# SoilCape.net
KiCad netlist of a schematic drawn in EAGLE
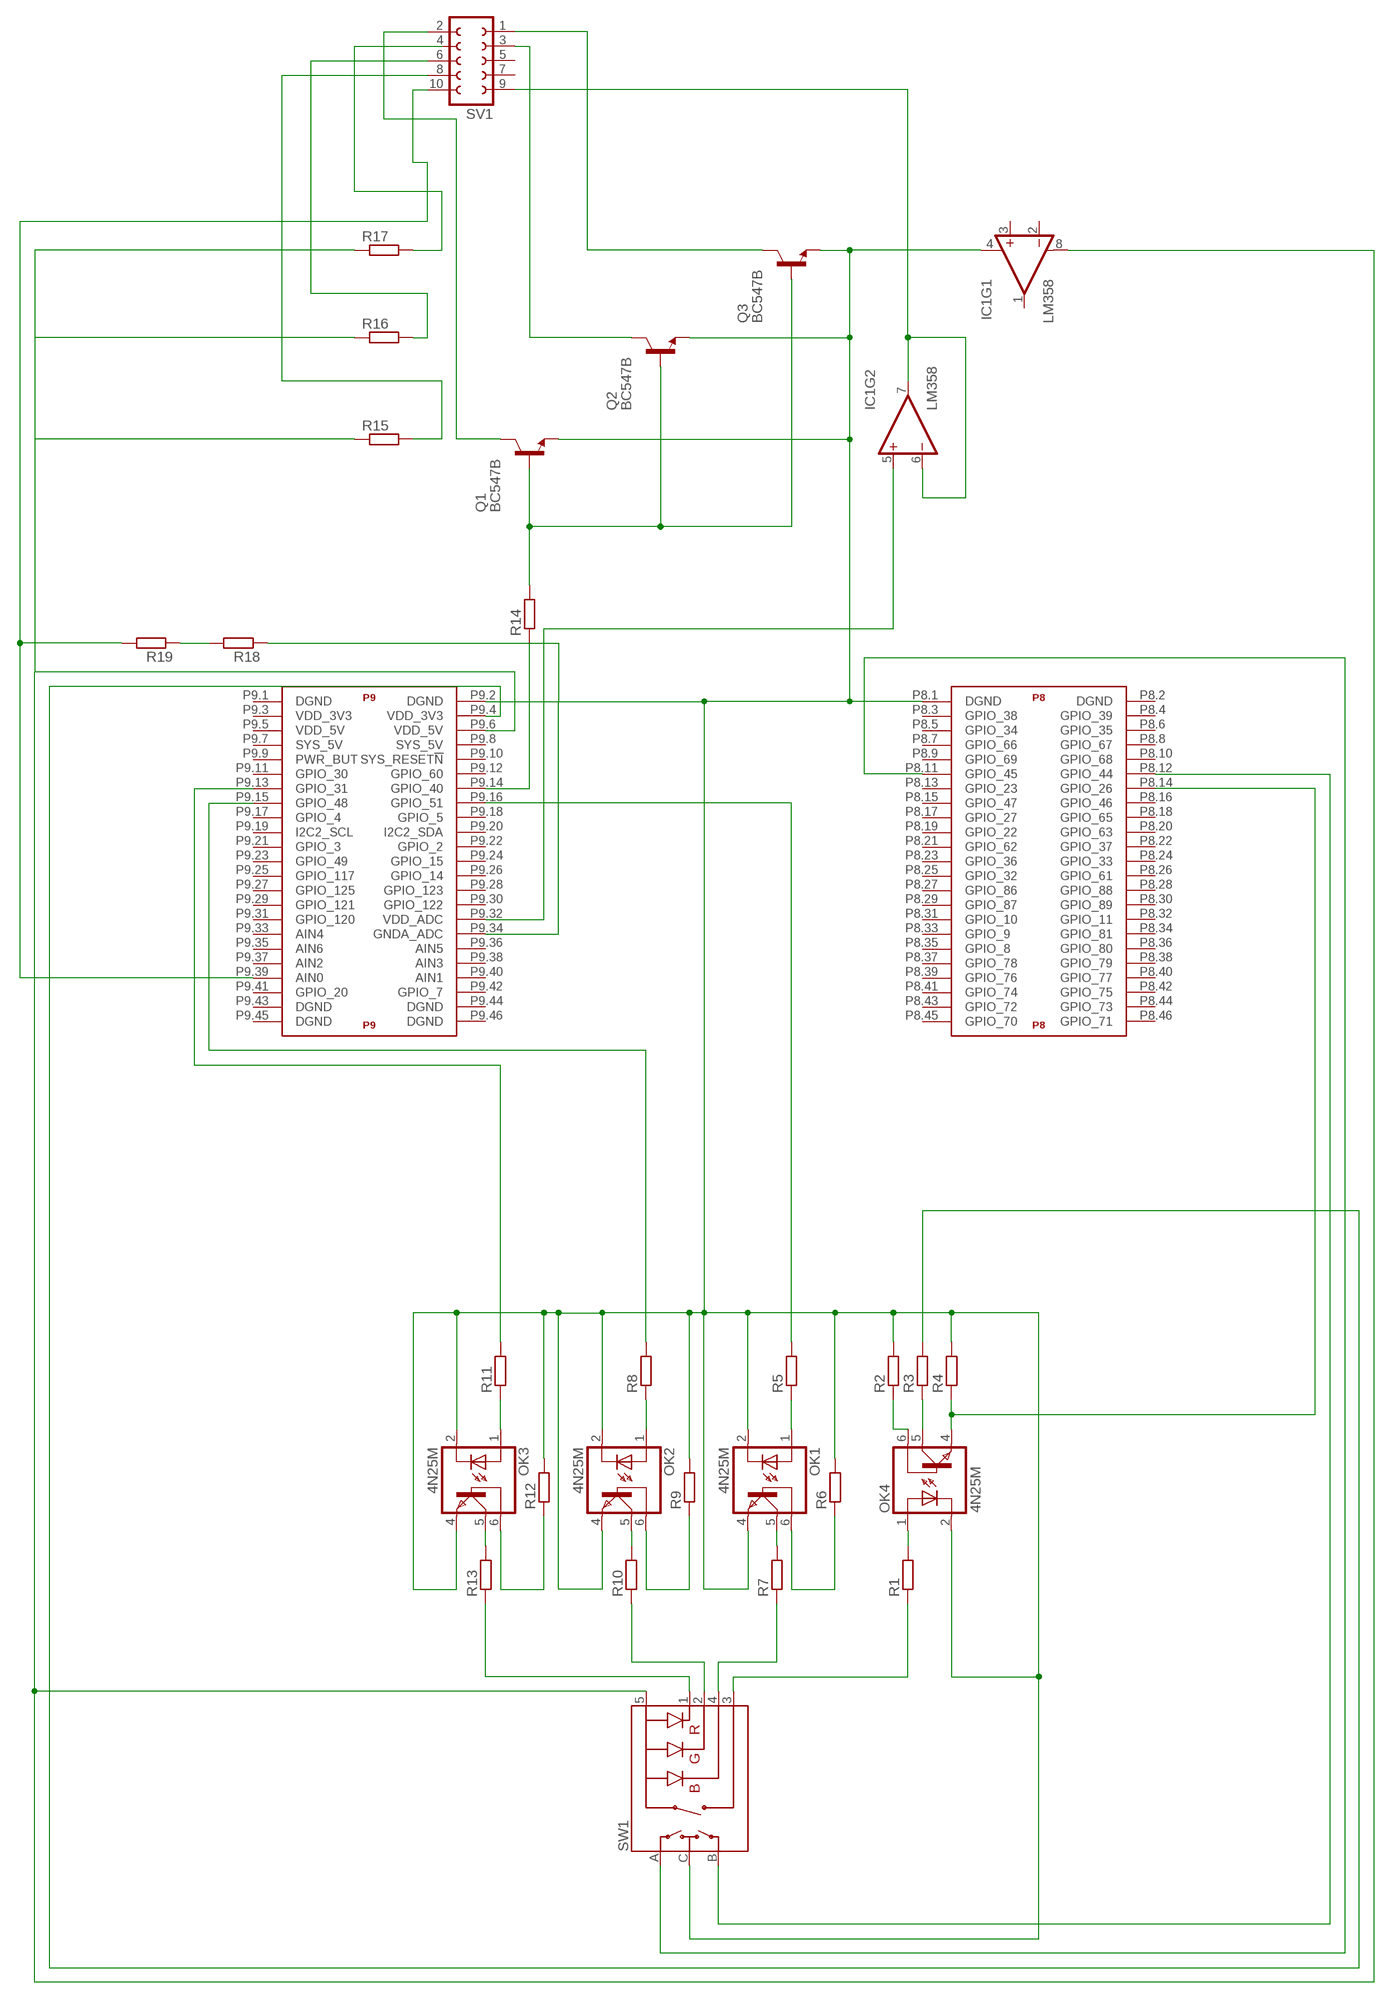
[diagram p0: schematic, sheet 1]

(export (version "E")
  (design (tool "Eeschema 10.0.6"))
  (components
    (comp (ref "IC1")
      (value "LM358")
      (footprint "eagle-import:DIP08")
      (libsource (lib "eagle-import") (part "LM358"))
    )
    (comp (ref "OK1")
      (value "4N25M")
      (footprint "eagle-import:DIL06")
      (fields (field (name "MPN") "4N25-M"))
      (libsource (lib "eagle-import") (part "4N?M25"))
    )
    (comp (ref "OK2")
      (value "4N25M")
      (footprint "eagle-import:DIL06")
      (fields (field (name "MPN") "4N25-M"))
      (libsource (lib "eagle-import") (part "4N?M25"))
    )
    (comp (ref "OK3")
      (value "4N25M")
      (footprint "eagle-import:DIL06")
      (fields (field (name "MPN") "4N25-M"))
      (libsource (lib "eagle-import") (part "4N?M25"))
    )
    (comp (ref "OK4")
      (value "4N25M")
      (footprint "eagle-import:DIL06")
      (fields (field (name "MPN") "4N25-M"))
      (libsource (lib "eagle-import") (part "4N?M25"))
    )
    (comp (ref "Q1")
      (value "BC547B")
      (footprint "eagle-import:TO92")
      (libsource (lib "eagle-import") (part "BC547B"))
    )
    (comp (ref "Q2")
      (value "BC547B")
      (footprint "eagle-import:TO92")
      (libsource (lib "eagle-import") (part "BC547B"))
    )
    (comp (ref "Q3")
      (value "BC547B")
      (footprint "eagle-import:TO92")
      (libsource (lib "eagle-import") (part "BC547B"))
    )
    (comp (ref "R1")
      (value "R-EU_0204/7")
      (footprint "eagle-import:0204_7")
      (libsource (lib "eagle-import") (part "R-EU_0204/7"))
    )
    (comp (ref "R2")
      (value "R-EU_0204/7")
      (footprint "eagle-import:0204_7")
      (libsource (lib "eagle-import") (part "R-EU_0204/7"))
    )
    (comp (ref "R3")
      (value "R-EU_0204/7")
      (footprint "eagle-import:0204_7")
      (libsource (lib "eagle-import") (part "R-EU_0204/7"))
    )
    (comp (ref "R4")
      (value "R-EU_0204/7")
      (footprint "eagle-import:0204_7")
      (libsource (lib "eagle-import") (part "R-EU_0204/7"))
    )
    (comp (ref "R5")
      (value "R-EU_0204/7")
      (footprint "eagle-import:0204_7")
      (libsource (lib "eagle-import") (part "R-EU_0204/7"))
    )
    (comp (ref "R6")
      (value "R-EU_0204/7")
      (footprint "eagle-import:0204_7")
      (libsource (lib "eagle-import") (part "R-EU_0204/7"))
    )
    (comp (ref "R7")
      (value "R-EU_0204/7")
      (footprint "eagle-import:0204_7")
      (libsource (lib "eagle-import") (part "R-EU_0204/7"))
    )
    (comp (ref "R8")
      (value "R-EU_0204/7")
      (footprint "eagle-import:0204_7")
      (libsource (lib "eagle-import") (part "R-EU_0204/7"))
    )
    (comp (ref "R9")
      (value "R-EU_0204/7")
      (footprint "eagle-import:0204_7")
      (libsource (lib "eagle-import") (part "R-EU_0204/7"))
    )
    (comp (ref "R10")
      (value "R-EU_0204/7")
      (footprint "eagle-import:0204_7")
      (libsource (lib "eagle-import") (part "R-EU_0204/7"))
    )
    (comp (ref "R11")
      (value "R-EU_0204/7")
      (footprint "eagle-import:0204_7")
      (libsource (lib "eagle-import") (part "R-EU_0204/7"))
    )
    (comp (ref "R12")
      (value "R-EU_0204/7")
      (footprint "eagle-import:0204_7")
      (libsource (lib "eagle-import") (part "R-EU_0204/7"))
    )
    (comp (ref "R13")
      (value "R-EU_0204/7")
      (footprint "eagle-import:0204_7")
      (libsource (lib "eagle-import") (part "R-EU_0204/7"))
    )
    (comp (ref "R14")
      (value "R-EU_0204/7")
      (footprint "eagle-import:0204_7")
      (libsource (lib "eagle-import") (part "R-EU_0204/7"))
    )
    (comp (ref "R15")
      (value "R-EU_0204/7")
      (footprint "eagle-import:0204_7")
      (libsource (lib "eagle-import") (part "R-EU_0204/7"))
    )
    (comp (ref "R16")
      (value "R-EU_0204/7")
      (footprint "eagle-import:0204_7")
      (libsource (lib "eagle-import") (part "R-EU_0204/7"))
    )
    (comp (ref "R17")
      (value "R-EU_0204/7")
      (footprint "eagle-import:0204_7")
      (libsource (lib "eagle-import") (part "R-EU_0204/7"))
    )
    (comp (ref "R18")
      (value "R-EU_0204/7")
      (footprint "eagle-import:0204_7")
      (libsource (lib "eagle-import") (part "R-EU_0204/7"))
    )
    (comp (ref "R19")
      (value "R-EU_0204/7")
      (footprint "eagle-import:0204_7")
      (libsource (lib "eagle-import") (part "R-EU_0204/7"))
    )
    (comp (ref "SV1")
      (value "FE05-2")
      (footprint "eagle-import:FE05-2")
      (libsource (lib "eagle-import") (part "FE05-2"))
    )
    (comp (ref "SW1")
      (value "ENCODER_RGB_CA")
      (footprint "eagle-import:ENCODER_LED_3")
      (libsource (lib "eagle-import") (part "ENCODER_RGB_CA"))
    )
    (comp (ref "U$1")
      (value "BEAGLE_BONE_BLACK_CAPE")
      (footprint "eagle-import:BEAGLE_BONE_BLACK_CAPE")
      (libsource (lib "eagle-import") (part "BEAGLE_BONE_BLACK_CAPE"))
    )
  )
  (nets
    (net (code "1") (name "Net-(IC1A-V+)") (class "Default")
      (node (ref "IC1") (pin "8") (pinfunction "V+_8") (pintype "power_in"))
      (node (ref "R15") (pin "1") (pinfunction "1_1") (pintype "passive"))
      (node (ref "R16") (pin "1") (pinfunction "1_1") (pintype "passive"))
      (node (ref "R17") (pin "1") (pinfunction "1_1") (pintype "passive"))
      (node (ref "SW1") (pin "5") (pinfunction "+_5") (pintype "passive"))
      (node (ref "U$1") (pin "P9.6") (pinfunction "VDD_5V_P9.6") (pintype "bidirectional"))
    )
    (net (code "2") (name "Net-(IC1A-V-)") (class "Default")
      (node (ref "IC1") (pin "4") (pinfunction "V-_4") (pintype "power_in"))
      (node (ref "OK1") (pin "2") (pinfunction "C_2") (pintype "passive"))
      (node (ref "OK1") (pin "4") (pinfunction "EMI_4") (pintype "passive"))
      (node (ref "OK2") (pin "2") (pinfunction "C_2") (pintype "passive"))
      (node (ref "OK2") (pin "4") (pinfunction "EMI_4") (pintype "passive"))
      (node (ref "OK3") (pin "2") (pinfunction "C_2") (pintype "passive"))
      (node (ref "OK3") (pin "4") (pinfunction "EMI_4") (pintype "passive"))
      (node (ref "OK4") (pin "2") (pinfunction "C_2") (pintype "passive"))
      (node (ref "Q1") (pin "1") (pinfunction "E_1") (pintype "passive"))
      (node (ref "Q2") (pin "1") (pinfunction "E_1") (pintype "passive"))
      (node (ref "Q3") (pin "1") (pinfunction "E_1") (pintype "passive"))
      (node (ref "R12") (pin "2") (pinfunction "2_2") (pintype "passive"))
      (node (ref "R18") (pin "1") (pinfunction "1_1") (pintype "passive"))
      (node (ref "R2") (pin "2") (pinfunction "2_2") (pintype "passive"))
      (node (ref "R4") (pin "2") (pinfunction "2_2") (pintype "passive"))
      (node (ref "R6") (pin "2") (pinfunction "2_2") (pintype "passive"))
      (node (ref "R9") (pin "2") (pinfunction "2_2") (pintype "passive"))
      (node (ref "SW1") (pin "C") (pinfunction "C_C") (pintype "bidirectional"))
      (node (ref "U$1") (pin "P8.1") (pinfunction "DGND_P8.1") (pintype "bidirectional"))
      (node (ref "U$1") (pin "P9.2") (pinfunction "DGND_P9.2") (pintype "bidirectional"))
      (node (ref "U$1") (pin "P9.34") (pinfunction "GNDA_ADC_P9.34") (pintype "bidirectional"))
    )
    (net (code "3") (name "Net-(IC1B-+IN)") (class "Default")
      (node (ref "IC1") (pin "5") (pinfunction "+IN_5") (pintype "input"))
      (node (ref "U$1") (pin "P9.32") (pinfunction "VDD_ADC_P9.32") (pintype "bidirectional"))
    )
    (net (code "4") (name "Net-(IC1B--IN)") (class "Default")
      (node (ref "IC1") (pin "6") (pinfunction "-IN_6") (pintype "input"))
      (node (ref "IC1") (pin "7") (pinfunction "OUT_7") (pintype "output"))
      (node (ref "SV1") (pin "9") (pinfunction "9_9") (pintype "passive"))
    )
    (net (code "5") (name "Net-(OK1-A)") (class "Default")
      (node (ref "OK1") (pin "1") (pinfunction "A_1") (pintype "passive"))
      (node (ref "R5") (pin "1") (pinfunction "1_1") (pintype "passive"))
    )
    (net (code "6") (name "Net-(OK1-BAS)") (class "Default")
      (node (ref "OK1") (pin "6") (pinfunction "BAS_6") (pintype "passive"))
      (node (ref "R6") (pin "1") (pinfunction "1_1") (pintype "passive"))
    )
    (net (code "7") (name "Net-(OK1-COL)") (class "Default")
      (node (ref "OK1") (pin "5") (pinfunction "COL_5") (pintype "passive"))
      (node (ref "R7") (pin "2") (pinfunction "2_2") (pintype "passive"))
    )
    (net (code "8") (name "Net-(OK2-A)") (class "Default")
      (node (ref "OK2") (pin "1") (pinfunction "A_1") (pintype "passive"))
      (node (ref "R8") (pin "1") (pinfunction "1_1") (pintype "passive"))
    )
    (net (code "9") (name "Net-(OK2-BAS)") (class "Default")
      (node (ref "OK2") (pin "6") (pinfunction "BAS_6") (pintype "passive"))
      (node (ref "R9") (pin "1") (pinfunction "1_1") (pintype "passive"))
    )
    (net (code "10") (name "Net-(OK2-COL)") (class "Default")
      (node (ref "OK2") (pin "5") (pinfunction "COL_5") (pintype "passive"))
      (node (ref "R10") (pin "2") (pinfunction "2_2") (pintype "passive"))
    )
    (net (code "11") (name "Net-(OK3-A)") (class "Default")
      (node (ref "OK3") (pin "1") (pinfunction "A_1") (pintype "passive"))
      (node (ref "R11") (pin "1") (pinfunction "1_1") (pintype "passive"))
    )
    (net (code "12") (name "Net-(OK3-BAS)") (class "Default")
      (node (ref "OK3") (pin "6") (pinfunction "BAS_6") (pintype "passive"))
      (node (ref "R12") (pin "1") (pinfunction "1_1") (pintype "passive"))
    )
    (net (code "13") (name "Net-(OK3-COL)") (class "Default")
      (node (ref "OK3") (pin "5") (pinfunction "COL_5") (pintype "passive"))
      (node (ref "R13") (pin "2") (pinfunction "2_2") (pintype "passive"))
    )
    (net (code "14") (name "Net-(OK4-A)") (class "Default")
      (node (ref "OK4") (pin "1") (pinfunction "A_1") (pintype "passive"))
      (node (ref "R1") (pin "2") (pinfunction "2_2") (pintype "passive"))
    )
    (net (code "15") (name "Net-(OK4-BAS)") (class "Default")
      (node (ref "OK4") (pin "6") (pinfunction "BAS_6") (pintype "passive"))
      (node (ref "R2") (pin "1") (pinfunction "1_1") (pintype "passive"))
    )
    (net (code "16") (name "Net-(OK4-COL)") (class "Default")
      (node (ref "OK4") (pin "5") (pinfunction "COL_5") (pintype "passive"))
      (node (ref "R3") (pin "1") (pinfunction "1_1") (pintype "passive"))
    )
    (net (code "17") (name "Net-(OK4-EMI)") (class "Default")
      (node (ref "OK4") (pin "4") (pinfunction "EMI_4") (pintype "passive"))
      (node (ref "R4") (pin "1") (pinfunction "1_1") (pintype "passive"))
      (node (ref "U$1") (pin "P8.14") (pinfunction "GPIO_26_P8.14") (pintype "bidirectional"))
    )
    (net (code "18") (name "Net-(Q1-B)") (class "Default")
      (node (ref "Q1") (pin "2") (pinfunction "B_2") (pintype "passive"))
      (node (ref "Q2") (pin "2") (pinfunction "B_2") (pintype "passive"))
      (node (ref "Q3") (pin "2") (pinfunction "B_2") (pintype "passive"))
      (node (ref "R14") (pin "2") (pinfunction "2_2") (pintype "passive"))
    )
    (net (code "19") (name "Net-(Q1-C)") (class "Default")
      (node (ref "Q1") (pin "3") (pinfunction "C_3") (pintype "passive"))
      (node (ref "SV1") (pin "2") (pinfunction "2_2") (pintype "passive"))
    )
    (net (code "20") (name "Net-(Q2-C)") (class "Default")
      (node (ref "Q2") (pin "3") (pinfunction "C_3") (pintype "passive"))
      (node (ref "SV1") (pin "3") (pinfunction "3_3") (pintype "passive"))
    )
    (net (code "21") (name "Net-(Q3-C)") (class "Default")
      (node (ref "Q3") (pin "3") (pinfunction "C_3") (pintype "passive"))
      (node (ref "SV1") (pin "1") (pinfunction "1_1") (pintype "passive"))
    )
    (net (code "22") (name "Net-(R3-Pad2)") (class "Default")
      (node (ref "R3") (pin "2") (pinfunction "2_2") (pintype "passive"))
      (node (ref "U$1") (pin "P9.4") (pinfunction "VDD_3V3_P9.4") (pintype "bidirectional"))
    )
    (net (code "23") (name "Net-(R15-Pad2)") (class "Default")
      (node (ref "R15") (pin "2") (pinfunction "2_2") (pintype "passive"))
      (node (ref "SV1") (pin "8") (pinfunction "8_8") (pintype "passive"))
    )
    (net (code "24") (name "Net-(R16-Pad2)") (class "Default")
      (node (ref "R16") (pin "2") (pinfunction "2_2") (pintype "passive"))
      (node (ref "SV1") (pin "6") (pinfunction "6_6") (pintype "passive"))
    )
    (net (code "25") (name "Net-(R17-Pad2)") (class "Default")
      (node (ref "R17") (pin "2") (pinfunction "2_2") (pintype "passive"))
      (node (ref "SV1") (pin "4") (pinfunction "4_4") (pintype "passive"))
    )
    (net (code "26") (name "Net-(R18-Pad2)") (class "Default")
      (node (ref "R18") (pin "2") (pinfunction "2_2") (pintype "passive"))
      (node (ref "R19") (pin "1") (pinfunction "1_1") (pintype "passive"))
    )
    (net (code "27") (name "Net-(SW1--B)") (class "Default")
      (node (ref "R7") (pin "1") (pinfunction "1_1") (pintype "passive"))
      (node (ref "SW1") (pin "4") (pinfunction "-B_4") (pintype "passive"))
    )
    (net (code "28") (name "Net-(SW1--G)") (class "Default")
      (node (ref "R10") (pin "1") (pinfunction "1_1") (pintype "passive"))
      (node (ref "SW1") (pin "2") (pinfunction "-G_2") (pintype "passive"))
    )
    (net (code "29") (name "Net-(SW1--R)") (class "Default")
      (node (ref "R13") (pin "1") (pinfunction "1_1") (pintype "passive"))
      (node (ref "SW1") (pin "1") (pinfunction "-R_1") (pintype "passive"))
    )
    (net (code "30") (name "Net-(SW1-SW)") (class "Default")
      (node (ref "R1") (pin "1") (pinfunction "1_1") (pintype "passive"))
      (node (ref "SW1") (pin "3") (pinfunction "SW_3") (pintype "passive"))
    )
    (net (code "31") (name "Net-(U$1A-GPIO_44)") (class "Default")
      (node (ref "SW1") (pin "B") (pinfunction "B_B") (pintype "bidirectional"))
      (node (ref "U$1") (pin "P8.12") (pinfunction "GPIO_44_P8.12") (pintype "bidirectional"))
    )
    (net (code "32") (name "Net-(U$1A-GPIO_45)") (class "Default")
      (node (ref "SW1") (pin "A") (pinfunction "A_A") (pintype "bidirectional"))
      (node (ref "U$1") (pin "P8.11") (pinfunction "GPIO_45_P8.11") (pintype "bidirectional"))
    )
    (net (code "33") (name "Net-(U$1B-AIN0)") (class "Default")
      (node (ref "R19") (pin "2") (pinfunction "2_2") (pintype "passive"))
      (node (ref "SV1") (pin "10") (pinfunction "10_10") (pintype "passive"))
      (node (ref "U$1") (pin "P9.39") (pinfunction "AIN0_P9.39") (pintype "bidirectional"))
    )
    (net (code "34") (name "Net-(U$1B-GPIO_31)") (class "Default")
      (node (ref "R11") (pin "2") (pinfunction "2_2") (pintype "passive"))
      (node (ref "U$1") (pin "P9.13") (pinfunction "GPIO_31_P9.13") (pintype "bidirectional"))
    )
    (net (code "35") (name "Net-(U$1B-GPIO_40)") (class "Default")
      (node (ref "R14") (pin "1") (pinfunction "1_1") (pintype "passive"))
      (node (ref "U$1") (pin "P9.14") (pinfunction "GPIO_40_P9.14") (pintype "bidirectional"))
    )
    (net (code "36") (name "Net-(U$1B-GPIO_48)") (class "Default")
      (node (ref "R8") (pin "2") (pinfunction "2_2") (pintype "passive"))
      (node (ref "U$1") (pin "P9.15") (pinfunction "GPIO_48_P9.15") (pintype "bidirectional"))
    )
    (net (code "37") (name "Net-(U$1B-GPIO_51)") (class "Default")
      (node (ref "R5") (pin "2") (pinfunction "2_2") (pintype "passive"))
      (node (ref "U$1") (pin "P9.16") (pinfunction "GPIO_51_P9.16") (pintype "bidirectional"))
    )
    (net (code "38") (name "unconnected-(IC1A-+IN-Pad3)") (class "Default")
      (node (ref "IC1") (pin "3") (pinfunction "+IN_3") (pintype "input"))
    )
    (net (code "39") (name "unconnected-(IC1A--IN-Pad2)") (class "Default")
      (node (ref "IC1") (pin "2") (pinfunction "-IN_2") (pintype "input"))
    )
    (net (code "40") (name "unconnected-(IC1A-OUT-Pad1)") (class "Default")
      (node (ref "IC1") (pin "1") (pinfunction "OUT_1") (pintype "output"))
    )
    (net (code "41") (name "unconnected-(SV1-Pad5)") (class "Default")
      (node (ref "SV1") (pin "5") (pinfunction "5_5") (pintype "passive"))
    )
    (net (code "42") (name "unconnected-(SV1-Pad7)") (class "Default")
      (node (ref "SV1") (pin "7") (pinfunction "7_7") (pintype "passive"))
    )
    (net (code "43") (name "unconnected-(U$1A-DGND-PadP8.2)") (class "Default")
      (node (ref "U$1") (pin "P8.2") (pinfunction "DGND_P8.2") (pintype "bidirectional"))
    )
    (net (code "44") (name "unconnected-(U$1A-GPIO_8-PadP8.35)") (class "Default")
      (node (ref "U$1") (pin "P8.35") (pinfunction "GPIO_8_P8.35") (pintype "bidirectional"))
    )
    (net (code "45") (name "unconnected-(U$1A-GPIO_9-PadP8.33)") (class "Default")
      (node (ref "U$1") (pin "P8.33") (pinfunction "GPIO_9_P8.33") (pintype "bidirectional"))
    )
    (net (code "46") (name "unconnected-(U$1A-GPIO_10-PadP8.31)") (class "Default")
      (node (ref "U$1") (pin "P8.31") (pinfunction "GPIO_10_P8.31") (pintype "bidirectional"))
    )
    (net (code "47") (name "unconnected-(U$1A-GPIO_11-PadP8.32)") (class "Default")
      (node (ref "U$1") (pin "P8.32") (pinfunction "GPIO_11_P8.32") (pintype "bidirectional"))
    )
    (net (code "48") (name "unconnected-(U$1A-GPIO_22-PadP8.19)") (class "Default")
      (node (ref "U$1") (pin "P8.19") (pinfunction "GPIO_22_P8.19") (pintype "bidirectional"))
    )
    (net (code "49") (name "unconnected-(U$1A-GPIO_23-PadP8.13)") (class "Default")
      (node (ref "U$1") (pin "P8.13") (pinfunction "GPIO_23_P8.13") (pintype "bidirectional"))
    )
    (net (code "50") (name "unconnected-(U$1A-GPIO_27-PadP8.17)") (class "Default")
      (node (ref "U$1") (pin "P8.17") (pinfunction "GPIO_27_P8.17") (pintype "bidirectional"))
    )
    (net (code "51") (name "unconnected-(U$1A-GPIO_32-PadP8.25)") (class "Default")
      (node (ref "U$1") (pin "P8.25") (pinfunction "GPIO_32_P8.25") (pintype "bidirectional"))
    )
    (net (code "52") (name "unconnected-(U$1A-GPIO_33-PadP8.24)") (class "Default")
      (node (ref "U$1") (pin "P8.24") (pinfunction "GPIO_33_P8.24") (pintype "bidirectional"))
    )
    (net (code "53") (name "unconnected-(U$1A-GPIO_34-PadP8.5)") (class "Default")
      (node (ref "U$1") (pin "P8.5") (pinfunction "GPIO_34_P8.5") (pintype "bidirectional"))
    )
    (net (code "54") (name "unconnected-(U$1A-GPIO_35-PadP8.6)") (class "Default")
      (node (ref "U$1") (pin "P8.6") (pinfunction "GPIO_35_P8.6") (pintype "bidirectional"))
    )
    (net (code "55") (name "unconnected-(U$1A-GPIO_36-PadP8.23)") (class "Default")
      (node (ref "U$1") (pin "P8.23") (pinfunction "GPIO_36_P8.23") (pintype "bidirectional"))
    )
    (net (code "56") (name "unconnected-(U$1A-GPIO_37-PadP8.22)") (class "Default")
      (node (ref "U$1") (pin "P8.22") (pinfunction "GPIO_37_P8.22") (pintype "bidirectional"))
    )
    (net (code "57") (name "unconnected-(U$1A-GPIO_38-PadP8.3)") (class "Default")
      (node (ref "U$1") (pin "P8.3") (pinfunction "GPIO_38_P8.3") (pintype "bidirectional"))
    )
    (net (code "58") (name "unconnected-(U$1A-GPIO_39-PadP8.4)") (class "Default")
      (node (ref "U$1") (pin "P8.4") (pinfunction "GPIO_39_P8.4") (pintype "bidirectional"))
    )
    (net (code "59") (name "unconnected-(U$1A-GPIO_46-PadP8.16)") (class "Default")
      (node (ref "U$1") (pin "P8.16") (pinfunction "GPIO_46_P8.16") (pintype "bidirectional"))
    )
    (net (code "60") (name "unconnected-(U$1A-GPIO_47-PadP8.15)") (class "Default")
      (node (ref "U$1") (pin "P8.15") (pinfunction "GPIO_47_P8.15") (pintype "bidirectional"))
    )
    (net (code "61") (name "unconnected-(U$1A-GPIO_61-PadP8.26)") (class "Default")
      (node (ref "U$1") (pin "P8.26") (pinfunction "GPIO_61_P8.26") (pintype "bidirectional"))
    )
    (net (code "62") (name "unconnected-(U$1A-GPIO_62-PadP8.21)") (class "Default")
      (node (ref "U$1") (pin "P8.21") (pinfunction "GPIO_62_P8.21") (pintype "bidirectional"))
    )
    (net (code "63") (name "unconnected-(U$1A-GPIO_63-PadP8.20)") (class "Default")
      (node (ref "U$1") (pin "P8.20") (pinfunction "GPIO_63_P8.20") (pintype "bidirectional"))
    )
    (net (code "64") (name "unconnected-(U$1A-GPIO_65-PadP8.18)") (class "Default")
      (node (ref "U$1") (pin "P8.18") (pinfunction "GPIO_65_P8.18") (pintype "bidirectional"))
    )
    (net (code "65") (name "unconnected-(U$1A-GPIO_66-PadP8.7)") (class "Default")
      (node (ref "U$1") (pin "P8.7") (pinfunction "GPIO_66_P8.7") (pintype "bidirectional"))
    )
    (net (code "66") (name "unconnected-(U$1A-GPIO_67-PadP8.8)") (class "Default")
      (node (ref "U$1") (pin "P8.8") (pinfunction "GPIO_67_P8.8") (pintype "bidirectional"))
    )
    (net (code "67") (name "unconnected-(U$1A-GPIO_68-PadP8.10)") (class "Default")
      (node (ref "U$1") (pin "P8.10") (pinfunction "GPIO_68_P8.10") (pintype "bidirectional"))
    )
    (net (code "68") (name "unconnected-(U$1A-GPIO_69-PadP8.9)") (class "Default")
      (node (ref "U$1") (pin "P8.9") (pinfunction "GPIO_69_P8.9") (pintype "bidirectional"))
    )
    (net (code "69") (name "unconnected-(U$1A-GPIO_70-PadP8.45)") (class "Default")
      (node (ref "U$1") (pin "P8.45") (pinfunction "GPIO_70_P8.45") (pintype "bidirectional"))
    )
    (net (code "70") (name "unconnected-(U$1A-GPIO_71-PadP8.46)") (class "Default")
      (node (ref "U$1") (pin "P8.46") (pinfunction "GPIO_71_P8.46") (pintype "bidirectional"))
    )
    (net (code "71") (name "unconnected-(U$1A-GPIO_72-PadP8.43)") (class "Default")
      (node (ref "U$1") (pin "P8.43") (pinfunction "GPIO_72_P8.43") (pintype "bidirectional"))
    )
    (net (code "72") (name "unconnected-(U$1A-GPIO_73-PadP8.44)") (class "Default")
      (node (ref "U$1") (pin "P8.44") (pinfunction "GPIO_73_P8.44") (pintype "bidirectional"))
    )
    (net (code "73") (name "unconnected-(U$1A-GPIO_74-PadP8.41)") (class "Default")
      (node (ref "U$1") (pin "P8.41") (pinfunction "GPIO_74_P8.41") (pintype "bidirectional"))
    )
    (net (code "74") (name "unconnected-(U$1A-GPIO_75-PadP8.42)") (class "Default")
      (node (ref "U$1") (pin "P8.42") (pinfunction "GPIO_75_P8.42") (pintype "bidirectional"))
    )
    (net (code "75") (name "unconnected-(U$1A-GPIO_76-PadP8.39)") (class "Default")
      (node (ref "U$1") (pin "P8.39") (pinfunction "GPIO_76_P8.39") (pintype "bidirectional"))
    )
    (net (code "76") (name "unconnected-(U$1A-GPIO_77-PadP8.40)") (class "Default")
      (node (ref "U$1") (pin "P8.40") (pinfunction "GPIO_77_P8.40") (pintype "bidirectional"))
    )
    (net (code "77") (name "unconnected-(U$1A-GPIO_78-PadP8.37)") (class "Default")
      (node (ref "U$1") (pin "P8.37") (pinfunction "GPIO_78_P8.37") (pintype "bidirectional"))
    )
    (net (code "78") (name "unconnected-(U$1A-GPIO_79-PadP8.38)") (class "Default")
      (node (ref "U$1") (pin "P8.38") (pinfunction "GPIO_79_P8.38") (pintype "bidirectional"))
    )
    (net (code "79") (name "unconnected-(U$1A-GPIO_80-PadP8.36)") (class "Default")
      (node (ref "U$1") (pin "P8.36") (pinfunction "GPIO_80_P8.36") (pintype "bidirectional"))
    )
    (net (code "80") (name "unconnected-(U$1A-GPIO_81-PadP8.34)") (class "Default")
      (node (ref "U$1") (pin "P8.34") (pinfunction "GPIO_81_P8.34") (pintype "bidirectional"))
    )
    (net (code "81") (name "unconnected-(U$1A-GPIO_86-PadP8.27)") (class "Default")
      (node (ref "U$1") (pin "P8.27") (pinfunction "GPIO_86_P8.27") (pintype "bidirectional"))
    )
    (net (code "82") (name "unconnected-(U$1A-GPIO_87-PadP8.29)") (class "Default")
      (node (ref "U$1") (pin "P8.29") (pinfunction "GPIO_87_P8.29") (pintype "bidirectional"))
    )
    (net (code "83") (name "unconnected-(U$1A-GPIO_88-PadP8.28)") (class "Default")
      (node (ref "U$1") (pin "P8.28") (pinfunction "GPIO_88_P8.28") (pintype "bidirectional"))
    )
    (net (code "84") (name "unconnected-(U$1A-GPIO_89-PadP8.30)") (class "Default")
      (node (ref "U$1") (pin "P8.30") (pinfunction "GPIO_89_P8.30") (pintype "bidirectional"))
    )
    (net (code "85") (name "unconnected-(U$1B-AIN1-PadP9.40)") (class "Default")
      (node (ref "U$1") (pin "P9.40") (pinfunction "AIN1_P9.40") (pintype "bidirectional"))
    )
    (net (code "86") (name "unconnected-(U$1B-AIN2-PadP9.37)") (class "Default")
      (node (ref "U$1") (pin "P9.37") (pinfunction "AIN2_P9.37") (pintype "bidirectional"))
    )
    (net (code "87") (name "unconnected-(U$1B-AIN3-PadP9.38)") (class "Default")
      (node (ref "U$1") (pin "P9.38") (pinfunction "AIN3_P9.38") (pintype "bidirectional"))
    )
    (net (code "88") (name "unconnected-(U$1B-AIN4-PadP9.33)") (class "Default")
      (node (ref "U$1") (pin "P9.33") (pinfunction "AIN4_P9.33") (pintype "bidirectional"))
    )
    (net (code "89") (name "unconnected-(U$1B-AIN5-PadP9.36)") (class "Default")
      (node (ref "U$1") (pin "P9.36") (pinfunction "AIN5_P9.36") (pintype "bidirectional"))
    )
    (net (code "90") (name "unconnected-(U$1B-AIN6-PadP9.35)") (class "Default")
      (node (ref "U$1") (pin "P9.35") (pinfunction "AIN6_P9.35") (pintype "bidirectional"))
    )
    (net (code "91") (name "unconnected-(U$1B-DGND-PadP9.1)") (class "Default")
      (node (ref "U$1") (pin "P9.1") (pinfunction "DGND_P9.1") (pintype "bidirectional"))
    )
    (net (code "92") (name "unconnected-(U$1B-DGND-PadP9.43)") (class "Default")
      (node (ref "U$1") (pin "P9.43") (pinfunction "DGND_P9.43") (pintype "bidirectional"))
    )
    (net (code "93") (name "unconnected-(U$1B-DGND-PadP9.44)") (class "Default")
      (node (ref "U$1") (pin "P9.44") (pinfunction "DGND_P9.44") (pintype "bidirectional"))
    )
    (net (code "94") (name "unconnected-(U$1B-DGND-PadP9.45)") (class "Default")
      (node (ref "U$1") (pin "P9.45") (pinfunction "DGND_P9.45") (pintype "bidirectional"))
    )
    (net (code "95") (name "unconnected-(U$1B-DGND-PadP9.46)") (class "Default")
      (node (ref "U$1") (pin "P9.46") (pinfunction "DGND_P9.46") (pintype "bidirectional"))
    )
    (net (code "96") (name "unconnected-(U$1B-GPIO_2-PadP9.22)") (class "Default")
      (node (ref "U$1") (pin "P9.22") (pinfunction "GPIO_2_P9.22") (pintype "bidirectional"))
    )
    (net (code "97") (name "unconnected-(U$1B-GPIO_3-PadP9.21)") (class "Default")
      (node (ref "U$1") (pin "P9.21") (pinfunction "GPIO_3_P9.21") (pintype "bidirectional"))
    )
    (net (code "98") (name "unconnected-(U$1B-GPIO_4-PadP9.17)") (class "Default")
      (node (ref "U$1") (pin "P9.17") (pinfunction "GPIO_4_P9.17") (pintype "bidirectional"))
    )
    (net (code "99") (name "unconnected-(U$1B-GPIO_5-PadP9.18)") (class "Default")
      (node (ref "U$1") (pin "P9.18") (pinfunction "GPIO_5_P9.18") (pintype "bidirectional"))
    )
    (net (code "100") (name "unconnected-(U$1B-GPIO_7-PadP9.42)") (class "Default")
      (node (ref "U$1") (pin "P9.42") (pinfunction "GPIO_7_P9.42") (pintype "bidirectional"))
    )
    (net (code "101") (name "unconnected-(U$1B-GPIO_14-PadP9.26)") (class "Default")
      (node (ref "U$1") (pin "P9.26") (pinfunction "GPIO_14_P9.26") (pintype "bidirectional"))
    )
    (net (code "102") (name "unconnected-(U$1B-GPIO_15-PadP9.24)") (class "Default")
      (node (ref "U$1") (pin "P9.24") (pinfunction "GPIO_15_P9.24") (pintype "bidirectional"))
    )
    (net (code "103") (name "unconnected-(U$1B-GPIO_20-PadP9.41)") (class "Default")
      (node (ref "U$1") (pin "P9.41") (pinfunction "GPIO_20_P9.41") (pintype "bidirectional"))
    )
    (net (code "104") (name "unconnected-(U$1B-GPIO_30-PadP9.11)") (class "Default")
      (node (ref "U$1") (pin "P9.11") (pinfunction "GPIO_30_P9.11") (pintype "bidirectional"))
    )
    (net (code "105") (name "unconnected-(U$1B-GPIO_49-PadP9.23)") (class "Default")
      (node (ref "U$1") (pin "P9.23") (pinfunction "GPIO_49_P9.23") (pintype "bidirectional"))
    )
    (net (code "106") (name "unconnected-(U$1B-GPIO_60-PadP9.12)") (class "Default")
      (node (ref "U$1") (pin "P9.12") (pinfunction "GPIO_60_P9.12") (pintype "bidirectional"))
    )
    (net (code "107") (name "unconnected-(U$1B-GPIO_117-PadP9.25)") (class "Default")
      (node (ref "U$1") (pin "P9.25") (pinfunction "GPIO_117_P9.25") (pintype "bidirectional"))
    )
    (net (code "108") (name "unconnected-(U$1B-GPIO_120-PadP9.31)") (class "Default")
      (node (ref "U$1") (pin "P9.31") (pinfunction "GPIO_120_P9.31") (pintype "bidirectional"))
    )
    (net (code "109") (name "unconnected-(U$1B-GPIO_121-PadP9.29)") (class "Default")
      (node (ref "U$1") (pin "P9.29") (pinfunction "GPIO_121_P9.29") (pintype "bidirectional"))
    )
    (net (code "110") (name "unconnected-(U$1B-GPIO_122-PadP9.30)") (class "Default")
      (node (ref "U$1") (pin "P9.30") (pinfunction "GPIO_122_P9.30") (pintype "bidirectional"))
    )
    (net (code "111") (name "unconnected-(U$1B-GPIO_123-PadP9.28)") (class "Default")
      (node (ref "U$1") (pin "P9.28") (pinfunction "GPIO_123_P9.28") (pintype "bidirectional"))
    )
    (net (code "112") (name "unconnected-(U$1B-GPIO_125-PadP9.27)") (class "Default")
      (node (ref "U$1") (pin "P9.27") (pinfunction "GPIO_125_P9.27") (pintype "bidirectional"))
    )
    (net (code "113") (name "unconnected-(U$1B-I2C2_SCL-PadP9.19)") (class "Default")
      (node (ref "U$1") (pin "P9.19") (pinfunction "I2C2_SCL_P9.19") (pintype "bidirectional"))
    )
    (net (code "114") (name "unconnected-(U$1B-I2C2_SDA-PadP9.20)") (class "Default")
      (node (ref "U$1") (pin "P9.20") (pinfunction "I2C2_SDA_P9.20") (pintype "bidirectional"))
    )
    (net (code "115") (name "unconnected-(U$1B-PWR_BUT-PadP9.9)") (class "Default")
      (node (ref "U$1") (pin "P9.9") (pinfunction "PWR_BUT_P9.9") (pintype "bidirectional"))
    )
    (net (code "116") (name "unconnected-(U$1B-SYS_5V-PadP9.7)") (class "Default")
      (node (ref "U$1") (pin "P9.7") (pinfunction "SYS_5V_P9.7") (pintype "bidirectional"))
    )
    (net (code "117") (name "unconnected-(U$1B-SYS_5V-PadP9.8)") (class "Default")
      (node (ref "U$1") (pin "P9.8") (pinfunction "SYS_5V_P9.8") (pintype "bidirectional"))
    )
    (net (code "118") (name "unconnected-(U$1B-SYS_RESET~{N}-PadP9.10)") (class "Default")
      (node (ref "U$1") (pin "P9.10") (pinfunction "SYS_RESET~{N}_P9.10") (pintype "bidirectional"))
    )
    (net (code "119") (name "unconnected-(U$1B-VDD_3V3-PadP9.3)") (class "Default")
      (node (ref "U$1") (pin "P9.3") (pinfunction "VDD_3V3_P9.3") (pintype "bidirectional"))
    )
    (net (code "120") (name "unconnected-(U$1B-VDD_5V-PadP9.5)") (class "Default")
      (node (ref "U$1") (pin "P9.5") (pinfunction "VDD_5V_P9.5") (pintype "bidirectional"))
    )
  )
)
